# ProProject_485__V11_2025-04-04.net
KiCad netlist of a schematic drawn in EasyEDA Pro
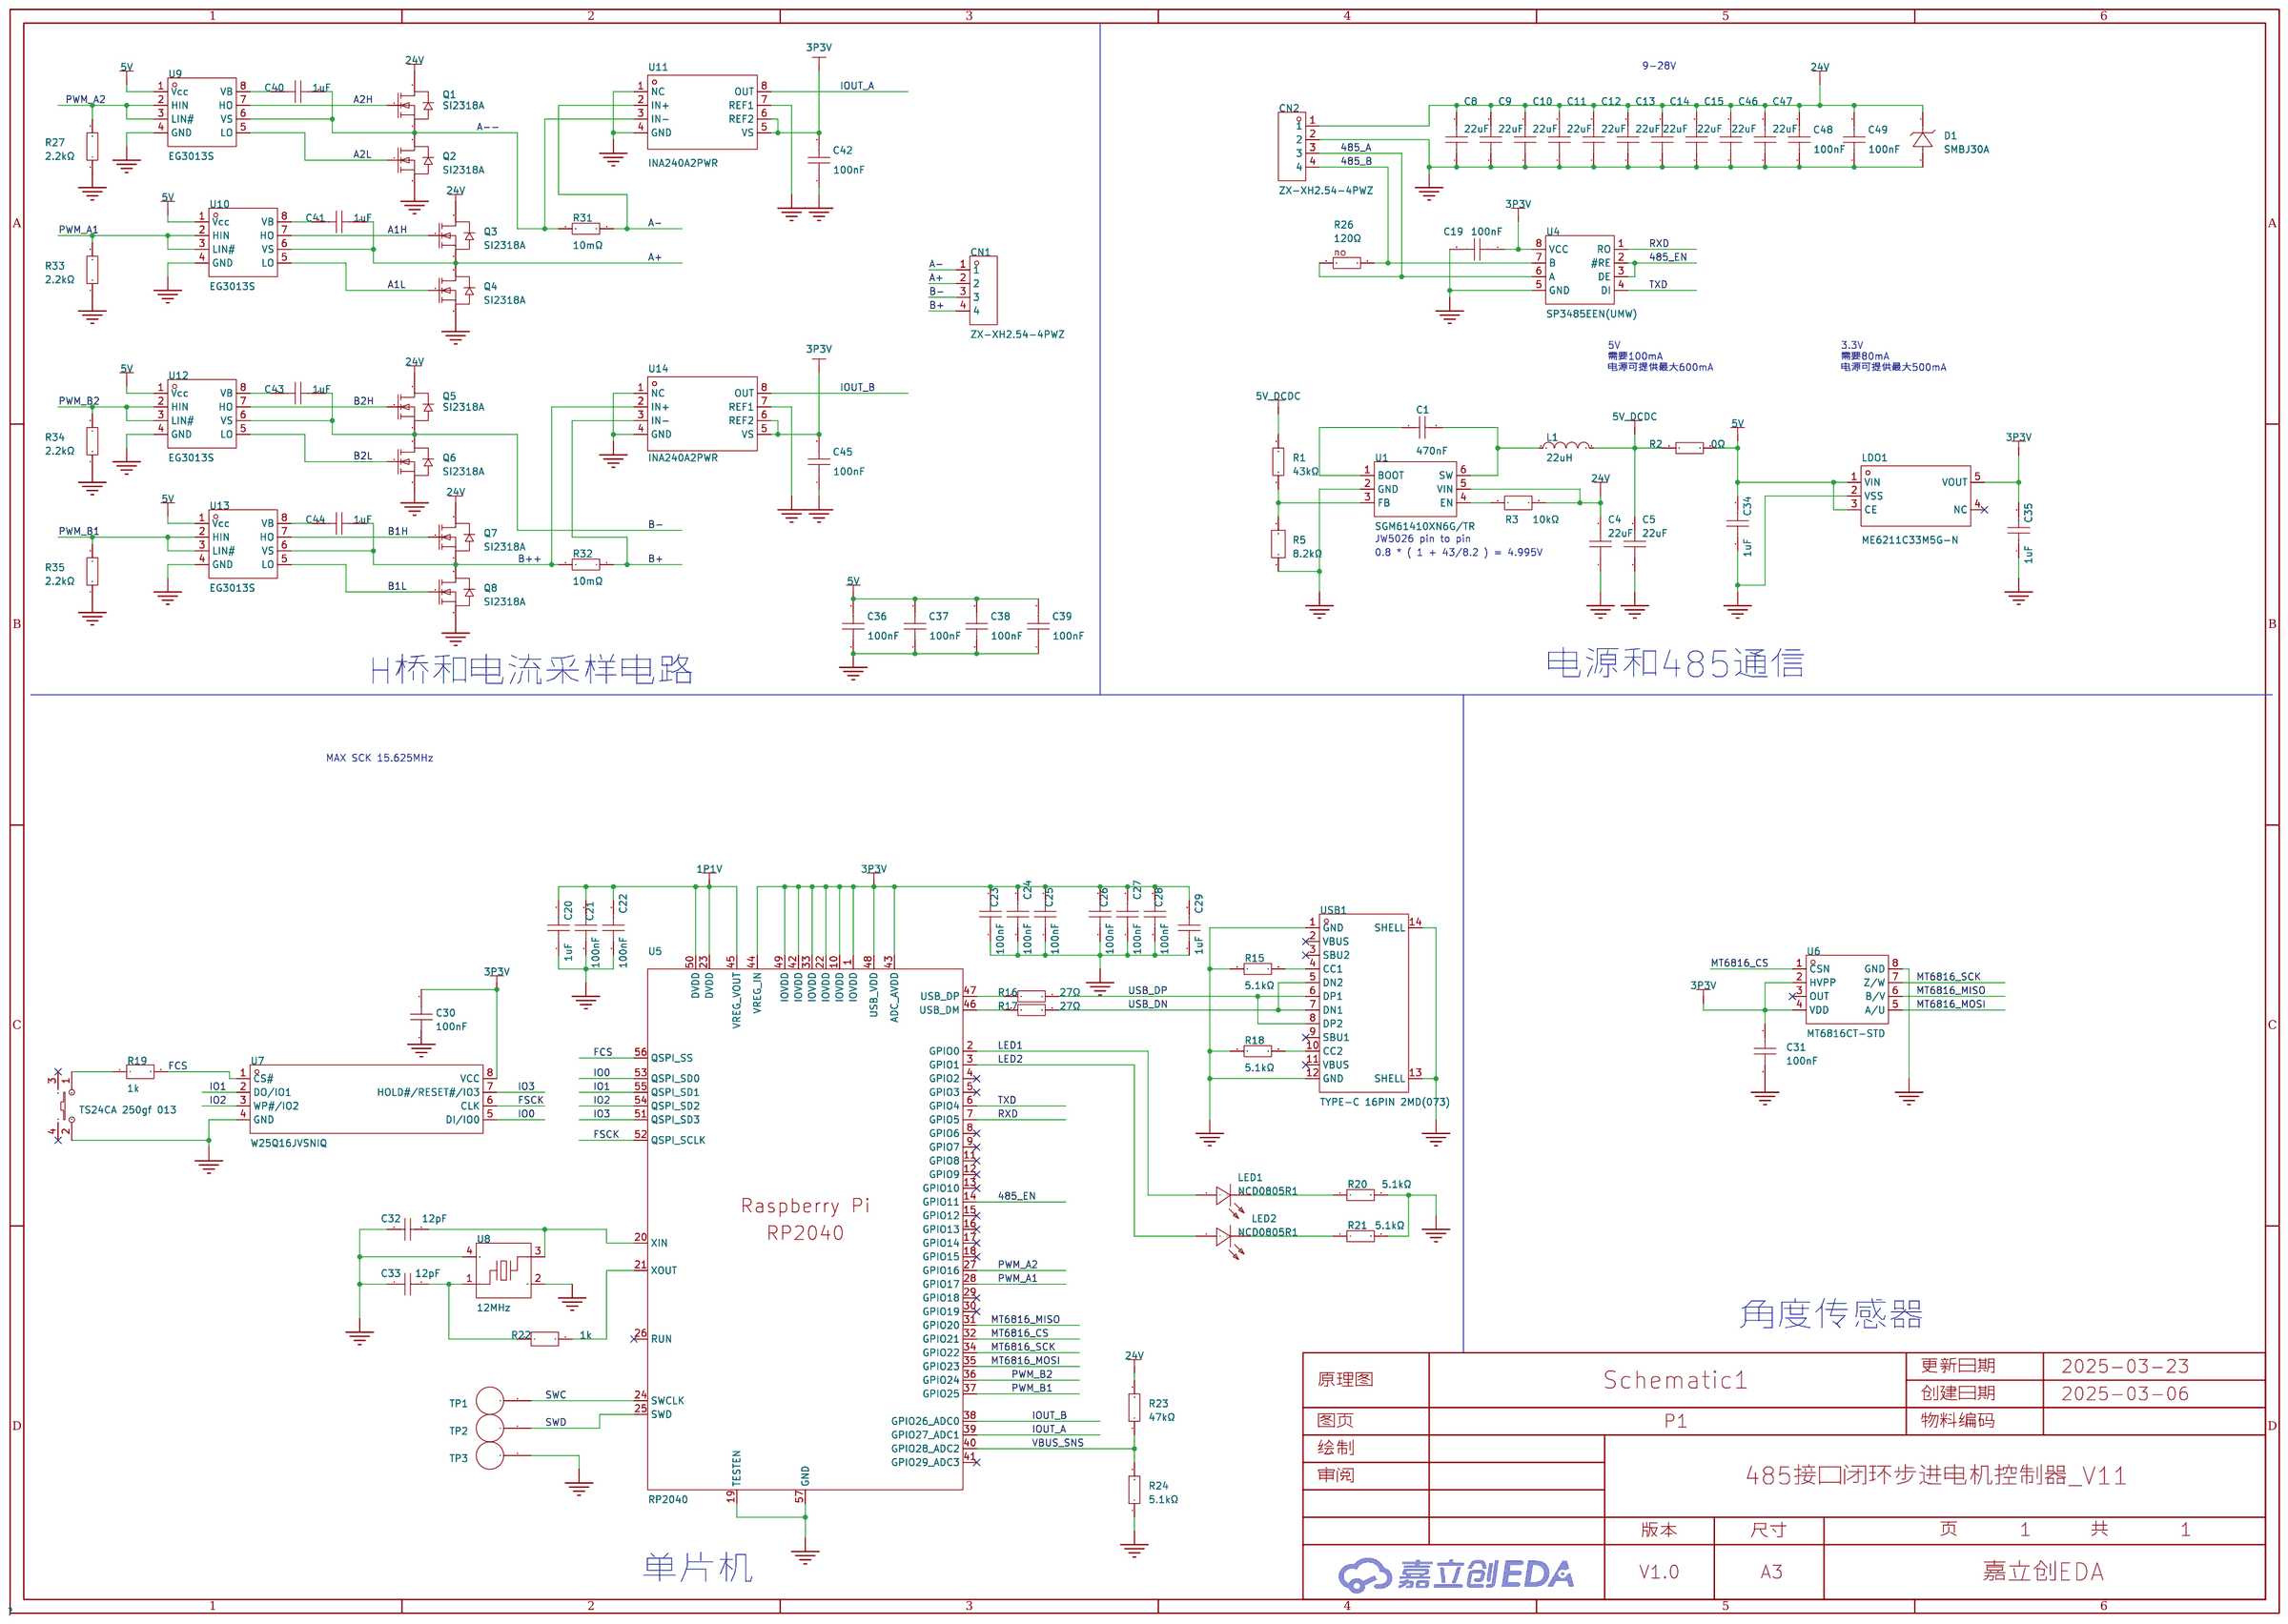
[diagram p0: schematic sheet]

(export (version "E")
  (design (tool "Eeschema 10.0.6"))
  (components
    (comp (ref "C1")
      (value "470nF")
      (footprint "easyedapro:C0603")
      (description "容值:470nF;精度:±10%;额定电压:25V;材质(温度系数):X7R;")
      (fields
        (field (name "Manufacturer Part") "CL10B474KA8NNNC")
        (field (name "Manufacturer") "SAMSUNG(三星)")
      )
      (libsource (lib "easyedapro") (part "CL10B474KA8NNNC"))
    )
    (comp (ref "C4")
      (value "22uF")
      (footprint "easyedapro:C0805")
      (description "容值:22uF;精度:±20%;额定电压:35V;材质(温度系数):X5R;")
      (fields
        (field (name "Manufacturer Part") "CGA0805X5R226M350MT")
        (field (name "Manufacturer") "HRE(芯声)")
      )
      (libsource (lib "easyedapro") (part "CGA0805X5R226M350MT"))
    )
    (comp (ref "C5")
      (value "22uF")
      (footprint "easyedapro:C0805")
      (description "容值:22uF;精度:±20%;额定电压:35V;材质(温度系数):X5R;")
      (fields
        (field (name "Manufacturer Part") "CGA0805X5R226M350MT")
        (field (name "Manufacturer") "HRE(芯声)")
      )
      (libsource (lib "easyedapro") (part "CGA0805X5R226M350MT"))
    )
    (comp (ref "C8")
      (value "22uF")
      (footprint "easyedapro:C0805")
      (description "容值:22uF;精度:±20%;额定电压:35V;材质(温度系数):X5R;")
      (fields
        (field (name "Manufacturer Part") "CGA0805X5R226M350MT")
        (field (name "Manufacturer") "HRE(芯声)")
      )
      (libsource (lib "easyedapro") (part "CGA0805X5R226M350MT"))
    )
    (comp (ref "C9")
      (value "22uF")
      (footprint "easyedapro:C0805")
      (description "容值:22uF;精度:±20%;额定电压:35V;材质(温度系数):X5R;")
      (fields
        (field (name "Manufacturer Part") "CGA0805X5R226M350MT")
        (field (name "Manufacturer") "HRE(芯声)")
      )
      (libsource (lib "easyedapro") (part "CGA0805X5R226M350MT"))
    )
    (comp (ref "C10")
      (value "22uF")
      (footprint "easyedapro:C0805")
      (description "容值:22uF;精度:±20%;额定电压:35V;材质(温度系数):X5R;")
      (fields
        (field (name "Manufacturer Part") "CGA0805X5R226M350MT")
        (field (name "Manufacturer") "HRE(芯声)")
      )
      (libsource (lib "easyedapro") (part "CGA0805X5R226M350MT"))
    )
    (comp (ref "C11")
      (value "22uF")
      (footprint "easyedapro:C0805")
      (description "容值:22uF;精度:±20%;额定电压:35V;材质(温度系数):X5R;")
      (fields
        (field (name "Manufacturer Part") "CGA0805X5R226M350MT")
        (field (name "Manufacturer") "HRE(芯声)")
      )
      (libsource (lib "easyedapro") (part "CGA0805X5R226M350MT"))
    )
    (comp (ref "C12")
      (value "22uF")
      (footprint "easyedapro:C0805")
      (description "容值:22uF;精度:±20%;额定电压:35V;材质(温度系数):X5R;")
      (fields
        (field (name "Manufacturer Part") "CGA0805X5R226M350MT")
        (field (name "Manufacturer") "HRE(芯声)")
      )
      (libsource (lib "easyedapro") (part "CGA0805X5R226M350MT"))
    )
    (comp (ref "C13")
      (value "22uF")
      (footprint "easyedapro:C0805")
      (description "容值:22uF;精度:±20%;额定电压:35V;材质(温度系数):X5R;")
      (fields
        (field (name "Manufacturer Part") "CGA0805X5R226M350MT")
        (field (name "Manufacturer") "HRE(芯声)")
      )
      (libsource (lib "easyedapro") (part "CGA0805X5R226M350MT"))
    )
    (comp (ref "C14")
      (value "22uF")
      (footprint "easyedapro:C0805")
      (description "容值:22uF;精度:±20%;额定电压:35V;材质(温度系数):X5R;")
      (fields
        (field (name "Manufacturer Part") "CGA0805X5R226M350MT")
        (field (name "Manufacturer") "HRE(芯声)")
      )
      (libsource (lib "easyedapro") (part "CGA0805X5R226M350MT"))
    )
    (comp (ref "C15")
      (value "22uF")
      (footprint "easyedapro:C0805")
      (description "容值:22uF;精度:±20%;额定电压:35V;材质(温度系数):X5R;")
      (fields
        (field (name "Manufacturer Part") "CGA0805X5R226M350MT")
        (field (name "Manufacturer") "HRE(芯声)")
      )
      (libsource (lib "easyedapro") (part "CGA0805X5R226M350MT"))
    )
    (comp (ref "C19")
      (value "100nF")
      (footprint "easyedapro:C0603")
      (description "容值:100nF;精度:±10%;额定电压:50V;材质(温度系数):X7R;")
      (fields
        (field (name "Manufacturer Part") "CC0603KRX7R9BB104")
        (field (name "Manufacturer") "YAGEO(国巨)")
      )
      (libsource (lib "easyedapro") (part "CC0603KRX7R9BB104"))
    )
    (comp (ref "C20")
      (value "1uF")
      (footprint "easyedapro:C0603")
      (description "容值:1uF;精度:±10%;额定电压:50V;材质(温度系数):X5R;")
      (fields
        (field (name "Manufacturer Part") "CL10A105KB8NNNC")
        (field (name "Manufacturer") "SAMSUNG(三星)")
      )
      (libsource (lib "easyedapro") (part "CL10A105KB8NNNC"))
    )
    (comp (ref "C21")
      (value "100nF")
      (footprint "easyedapro:C0603")
      (description "容值:100nF;精度:±10%;额定电压:50V;材质(温度系数):X7R;")
      (fields
        (field (name "Manufacturer Part") "CC0603KRX7R9BB104")
        (field (name "Manufacturer") "YAGEO(国巨)")
      )
      (libsource (lib "easyedapro") (part "CC0603KRX7R9BB104"))
    )
    (comp (ref "C22")
      (value "100nF")
      (footprint "easyedapro:C0603")
      (description "容值:100nF;精度:±10%;额定电压:50V;材质(温度系数):X7R;")
      (fields
        (field (name "Manufacturer Part") "CC0603KRX7R9BB104")
        (field (name "Manufacturer") "YAGEO(国巨)")
      )
      (libsource (lib "easyedapro") (part "CC0603KRX7R9BB104"))
    )
    (comp (ref "C23")
      (value "100nF")
      (footprint "easyedapro:C0603")
      (description "容值:100nF;精度:±10%;额定电压:50V;材质(温度系数):X7R;")
      (fields
        (field (name "Manufacturer Part") "CC0603KRX7R9BB104")
        (field (name "Manufacturer") "YAGEO(国巨)")
      )
      (libsource (lib "easyedapro") (part "CC0603KRX7R9BB104"))
    )
    (comp (ref "C24")
      (value "100nF")
      (footprint "easyedapro:C0603")
      (description "容值:100nF;精度:±10%;额定电压:50V;材质(温度系数):X7R;")
      (fields
        (field (name "Manufacturer Part") "CC0603KRX7R9BB104")
        (field (name "Manufacturer") "YAGEO(国巨)")
      )
      (libsource (lib "easyedapro") (part "CC0603KRX7R9BB104"))
    )
    (comp (ref "C25")
      (value "100nF")
      (footprint "easyedapro:C0603")
      (description "容值:100nF;精度:±10%;额定电压:50V;材质(温度系数):X7R;")
      (fields
        (field (name "Manufacturer Part") "CC0603KRX7R9BB104")
        (field (name "Manufacturer") "YAGEO(国巨)")
      )
      (libsource (lib "easyedapro") (part "CC0603KRX7R9BB104"))
    )
    (comp (ref "C26")
      (value "100nF")
      (footprint "easyedapro:C0603")
      (description "容值:100nF;精度:±10%;额定电压:50V;材质(温度系数):X7R;")
      (fields
        (field (name "Manufacturer Part") "CC0603KRX7R9BB104")
        (field (name "Manufacturer") "YAGEO(国巨)")
      )
      (libsource (lib "easyedapro") (part "CC0603KRX7R9BB104"))
    )
    (comp (ref "C27")
      (value "100nF")
      (footprint "easyedapro:C0603")
      (description "容值:100nF;精度:±10%;额定电压:50V;材质(温度系数):X7R;")
      (fields
        (field (name "Manufacturer Part") "CC0603KRX7R9BB104")
        (field (name "Manufacturer") "YAGEO(国巨)")
      )
      (libsource (lib "easyedapro") (part "CC0603KRX7R9BB104"))
    )
    (comp (ref "C28")
      (value "100nF")
      (footprint "easyedapro:C0603")
      (description "容值:100nF;精度:±10%;额定电压:50V;材质(温度系数):X7R;")
      (fields
        (field (name "Manufacturer Part") "CC0603KRX7R9BB104")
        (field (name "Manufacturer") "YAGEO(国巨)")
      )
      (libsource (lib "easyedapro") (part "CC0603KRX7R9BB104"))
    )
    (comp (ref "C29")
      (value "1uF")
      (footprint "easyedapro:C0603")
      (description "容值:1uF;精度:±10%;额定电压:50V;材质(温度系数):X5R;")
      (fields
        (field (name "Manufacturer Part") "CL10A105KB8NNNC")
        (field (name "Manufacturer") "SAMSUNG(三星)")
      )
      (libsource (lib "easyedapro") (part "CL10A105KB8NNNC"))
    )
    (comp (ref "C30")
      (value "100nF")
      (footprint "easyedapro:C0603")
      (description "容值:100nF;精度:±10%;额定电压:50V;材质(温度系数):X7R;")
      (fields
        (field (name "Manufacturer Part") "CC0603KRX7R9BB104")
        (field (name "Manufacturer") "YAGEO(国巨)")
      )
      (libsource (lib "easyedapro") (part "CC0603KRX7R9BB104"))
    )
    (comp (ref "C31")
      (value "100nF")
      (footprint "easyedapro:C0603")
      (description "容值:100nF;精度:±10%;额定电压:50V;材质(温度系数):X7R;")
      (fields
        (field (name "Manufacturer Part") "CC0603KRX7R9BB104")
        (field (name "Manufacturer") "YAGEO(国巨)")
      )
      (libsource (lib "easyedapro") (part "CC0603KRX7R9BB104"))
    )
    (comp (ref "C32")
      (value "12pF")
      (footprint "easyedapro:C0603")
      (description "容值:12pF;精度:±5%;额定电压:50V;材质(温度系数):C0G;")
      (fields
        (field (name "Manufacturer Part") "CL10C120JB8NNNC")
        (field (name "Manufacturer") "SAMSUNG(三星)")
      )
      (libsource (lib "easyedapro") (part "CL10C120JB8NNNC"))
    )
    (comp (ref "C33")
      (value "12pF")
      (footprint "easyedapro:C0603")
      (description "容值:12pF;精度:±5%;额定电压:50V;材质(温度系数):C0G;")
      (fields
        (field (name "Manufacturer Part") "CL10C120JB8NNNC")
        (field (name "Manufacturer") "SAMSUNG(三星)")
      )
      (libsource (lib "easyedapro") (part "CL10C120JB8NNNC"))
    )
    (comp (ref "C34")
      (value "1uF")
      (footprint "easyedapro:C0603")
      (description "容值:1uF;精度:±10%;额定电压:50V;材质(温度系数):X5R;")
      (fields
        (field (name "Manufacturer Part") "CL10A105KB8NNNC")
        (field (name "Manufacturer") "SAMSUNG(三星)")
      )
      (libsource (lib "easyedapro") (part "CL10A105KB8NNNC"))
    )
    (comp (ref "C35")
      (value "1uF")
      (footprint "easyedapro:C0603")
      (description "容值:1uF;精度:±10%;额定电压:50V;材质(温度系数):X5R;")
      (fields
        (field (name "Manufacturer Part") "CL10A105KB8NNNC")
        (field (name "Manufacturer") "SAMSUNG(三星)")
      )
      (libsource (lib "easyedapro") (part "CL10A105KB8NNNC"))
    )
    (comp (ref "C36")
      (value "100nF")
      (footprint "easyedapro:C0603")
      (description "容值:100nF;精度:±10%;额定电压:50V;材质(温度系数):X7R;")
      (fields
        (field (name "Manufacturer Part") "CC0603KRX7R9BB104")
        (field (name "Manufacturer") "YAGEO(国巨)")
      )
      (libsource (lib "easyedapro") (part "CC0603KRX7R9BB104"))
    )
    (comp (ref "C37")
      (value "100nF")
      (footprint "easyedapro:C0603")
      (description "容值:100nF;精度:±10%;额定电压:50V;材质(温度系数):X7R;")
      (fields
        (field (name "Manufacturer Part") "CC0603KRX7R9BB104")
        (field (name "Manufacturer") "YAGEO(国巨)")
      )
      (libsource (lib "easyedapro") (part "CC0603KRX7R9BB104"))
    )
    (comp (ref "C38")
      (value "100nF")
      (footprint "easyedapro:C0603")
      (description "容值:100nF;精度:±10%;额定电压:50V;材质(温度系数):X7R;")
      (fields
        (field (name "Manufacturer Part") "CC0603KRX7R9BB104")
        (field (name "Manufacturer") "YAGEO(国巨)")
      )
      (libsource (lib "easyedapro") (part "CC0603KRX7R9BB104"))
    )
    (comp (ref "C39")
      (value "100nF")
      (footprint "easyedapro:C0603")
      (description "容值:100nF;精度:±10%;额定电压:50V;材质(温度系数):X7R;")
      (fields
        (field (name "Manufacturer Part") "CC0603KRX7R9BB104")
        (field (name "Manufacturer") "YAGEO(国巨)")
      )
      (libsource (lib "easyedapro") (part "CC0603KRX7R9BB104"))
    )
    (comp (ref "C40")
      (value "1uF")
      (footprint "easyedapro:C0603")
      (description "容值:1uF;精度:±10%;额定电压:50V;材质(温度系数):X5R;")
      (fields
        (field (name "Manufacturer Part") "CL10A105KB8NNNC")
        (field (name "Manufacturer") "SAMSUNG(三星)")
      )
      (libsource (lib "easyedapro") (part "CL10A105KB8NNNC"))
    )
    (comp (ref "C41")
      (value "1uF")
      (footprint "easyedapro:C0603")
      (description "容值:1uF;精度:±10%;额定电压:50V;材质(温度系数):X5R;")
      (fields
        (field (name "Manufacturer Part") "CL10A105KB8NNNC")
        (field (name "Manufacturer") "SAMSUNG(三星)")
      )
      (libsource (lib "easyedapro") (part "CL10A105KB8NNNC"))
    )
    (comp (ref "C42")
      (value "100nF")
      (footprint "easyedapro:C0603")
      (description "容值:100nF;精度:±10%;额定电压:50V;材质(温度系数):X7R;")
      (fields
        (field (name "Manufacturer Part") "CC0603KRX7R9BB104")
        (field (name "Manufacturer") "YAGEO(国巨)")
      )
      (libsource (lib "easyedapro") (part "CC0603KRX7R9BB104"))
    )
    (comp (ref "C43")
      (value "1uF")
      (footprint "easyedapro:C0603")
      (description "容值:1uF;精度:±10%;额定电压:50V;材质(温度系数):X5R;")
      (fields
        (field (name "Manufacturer Part") "CL10A105KB8NNNC")
        (field (name "Manufacturer") "SAMSUNG(三星)")
      )
      (libsource (lib "easyedapro") (part "CL10A105KB8NNNC"))
    )
    (comp (ref "C44")
      (value "1uF")
      (footprint "easyedapro:C0603")
      (description "容值:1uF;精度:±10%;额定电压:50V;材质(温度系数):X5R;")
      (fields
        (field (name "Manufacturer Part") "CL10A105KB8NNNC")
        (field (name "Manufacturer") "SAMSUNG(三星)")
      )
      (libsource (lib "easyedapro") (part "CL10A105KB8NNNC"))
    )
    (comp (ref "C45")
      (value "100nF")
      (footprint "easyedapro:C0603")
      (description "容值:100nF;精度:±10%;额定电压:50V;材质(温度系数):X7R;")
      (fields
        (field (name "Manufacturer Part") "CC0603KRX7R9BB104")
        (field (name "Manufacturer") "YAGEO(国巨)")
      )
      (libsource (lib "easyedapro") (part "CC0603KRX7R9BB104"))
    )
    (comp (ref "C46")
      (value "22uF")
      (footprint "easyedapro:C0805")
      (description "容值:22uF;精度:±20%;额定电压:35V;材质(温度系数):X5R;")
      (fields
        (field (name "Manufacturer Part") "CGA0805X5R226M350MT")
        (field (name "Manufacturer") "HRE(芯声)")
      )
      (libsource (lib "easyedapro") (part "CGA0805X5R226M350MT"))
    )
    (comp (ref "C47")
      (value "22uF")
      (footprint "easyedapro:C0805")
      (description "容值:22uF;精度:±20%;额定电压:35V;材质(温度系数):X5R;")
      (fields
        (field (name "Manufacturer Part") "CGA0805X5R226M350MT")
        (field (name "Manufacturer") "HRE(芯声)")
      )
      (libsource (lib "easyedapro") (part "CGA0805X5R226M350MT"))
    )
    (comp (ref "C48")
      (value "100nF")
      (footprint "easyedapro:C0603")
      (description "容值:100nF;精度:±10%;额定电压:50V;材质(温度系数):X7R;")
      (fields
        (field (name "Manufacturer Part") "CC0603KRX7R9BB104")
        (field (name "Manufacturer") "YAGEO(国巨)")
      )
      (libsource (lib "easyedapro") (part "CC0603KRX7R9BB104"))
    )
    (comp (ref "C49")
      (value "100nF")
      (footprint "easyedapro:C0603")
      (description "容值:100nF;精度:±10%;额定电压:50V;材质(温度系数):X7R;")
      (fields
        (field (name "Manufacturer Part") "CC0603KRX7R9BB104")
        (field (name "Manufacturer") "YAGEO(国巨)")
      )
      (libsource (lib "easyedapro") (part "CC0603KRX7R9BB104"))
    )
    (comp (ref "CN1")
      (value "ZX-XH2.54-4PWZ")
      (footprint "easyedapro:CONN-TH_4P-P2.50_ZX-XH2.54-4PWZ")
      (fields (field (name "Manufacturer") "Megastar(兆星)"))
      (libsource (lib "easyedapro") (part "ZX-XH2.54-4PWZ"))
    )
    (comp (ref "CN2")
      (value "ZX-XH2.54-4PWZ")
      (footprint "easyedapro:CONN-TH_4P-P2.50_ZX-XH2.54-4PWZ")
      (fields (field (name "Manufacturer") "Megastar(兆星)"))
      (libsource (lib "easyedapro") (part "ZX-XH2.54-4PWZ"))
    )
    (comp (ref "D1")
      (value "SMBJ30A")
      (footprint "easyedapro:SMB_L4.6-W3.6-LS5.4-RD")
      (description "极性:单向;反向截止电压(Vrwm):30V;钳位电压:48.4V;峰值脉冲电流(Ipp):12.4A;峰值脉冲功率(Ppp):600W;击穿电压:33.3V;")
      (fields (field (name "Manufacturer") "宏嘉诚"))
      (libsource (lib "easyedapro") (part "SMBJ30A_C19077584"))
    )
    (comp (ref "L1")
      (value "22uH")
      (footprint "easyedapro:IND-SMD_L4.0-W4.0")
      (description "电感值:22uH;精度:±20%;额定电流:1.1A;饱和电流(Isat):1.5A;")
      (fields
        (field (name "Manufacturer Part") "FHD4020S-220MT")
        (field (name "Manufacturer") "cjiang(长江微电)")
      )
      (libsource (lib "easyedapro") (part "FHD4020S-220MT"))
    )
    (comp (ref "LDO1")
      (value "ME6211C33M5G-N")
      (footprint "easyedapro:SOT-23-5_L3.0-W1.7-P0.95-LS2.8-BL")
      (description "输出类型:固定;最大输入电压:6V;输出电压:3.3V;最大输出电流:500mA;电源纹波抑制比(PSRR):70dB;输出极性:正极;")
      (fields (field (name "Manufacturer") "MICRONE(南京微盟)"))
      (libsource (lib "easyedapro") (part "ME6211C33M5G-N"))
    )
    (comp (ref "LED1")
      (value "NCD0805R1")
      (footprint "easyedapro:LED0805-R-RD")
      (fields (field (name "Manufacturer") "国星光电"))
      (libsource (lib "easyedapro") (part "FC-2012HRK-620D"))
    )
    (comp (ref "LED2")
      (value "NCD0805R1")
      (footprint "easyedapro:LED0805-R-RD")
      (fields (field (name "Manufacturer") "国星光电"))
      (libsource (lib "easyedapro") (part "FC-2012HRK-620D"))
    )
    (comp (ref "Q1")
      (value "SI2318A")
      (footprint "easyedapro:SOT-23-3_L2.9-W1.3-P1.90-LS2.4-BR")
      (fields (field (name "Manufacturer") "UMW(友台半导体)"))
      (libsource (lib "easyedapro") (part "SI2318A"))
    )
    (comp (ref "Q2")
      (value "SI2318A")
      (footprint "easyedapro:SOT-23-3_L2.9-W1.3-P1.90-LS2.4-BR")
      (fields (field (name "Manufacturer") "UMW(友台半导体)"))
      (libsource (lib "easyedapro") (part "SI2318A"))
    )
    (comp (ref "Q3")
      (value "SI2318A")
      (footprint "easyedapro:SOT-23-3_L2.9-W1.3-P1.90-LS2.4-BR")
      (fields (field (name "Manufacturer") "UMW(友台半导体)"))
      (libsource (lib "easyedapro") (part "SI2318A"))
    )
    (comp (ref "Q4")
      (value "SI2318A")
      (footprint "easyedapro:SOT-23-3_L2.9-W1.3-P1.90-LS2.4-BR")
      (fields (field (name "Manufacturer") "UMW(友台半导体)"))
      (libsource (lib "easyedapro") (part "SI2318A"))
    )
    (comp (ref "Q5")
      (value "SI2318A")
      (footprint "easyedapro:SOT-23-3_L2.9-W1.3-P1.90-LS2.4-BR")
      (fields (field (name "Manufacturer") "UMW(友台半导体)"))
      (libsource (lib "easyedapro") (part "SI2318A"))
    )
    (comp (ref "Q6")
      (value "SI2318A")
      (footprint "easyedapro:SOT-23-3_L2.9-W1.3-P1.90-LS2.4-BR")
      (fields (field (name "Manufacturer") "UMW(友台半导体)"))
      (libsource (lib "easyedapro") (part "SI2318A"))
    )
    (comp (ref "Q7")
      (value "SI2318A")
      (footprint "easyedapro:SOT-23-3_L2.9-W1.3-P1.90-LS2.4-BR")
      (fields (field (name "Manufacturer") "UMW(友台半导体)"))
      (libsource (lib "easyedapro") (part "SI2318A"))
    )
    (comp (ref "Q8")
      (value "SI2318A")
      (footprint "easyedapro:SOT-23-3_L2.9-W1.3-P1.90-LS2.4-BR")
      (fields (field (name "Manufacturer") "UMW(友台半导体)"))
      (libsource (lib "easyedapro") (part "SI2318A"))
    )
    (comp (ref "R1")
      (value "43kΩ")
      (footprint "easyedapro:R0603")
      (description "电阻类型:厚膜电阻;阻值:47kΩ;精度:±1%;功率:100mW;最大工作电压:75V;温度系数:±100ppm/°C;")
      (fields
        (field (name "Manufacturer Part") "0603WAF4302T5E")
        (field (name "Manufacturer") "UNI-ROYAL(厚声)")
      )
      (libsource (lib "easyedapro") (part "0603WAF4702T5E"))
    )
    (comp (ref "R2")
      (value "0Ω")
      (footprint "easyedapro:R0603")
      (description "电阻类型:厚膜电阻;阻值:0Ω;精度:±1%;功率:100mW;最大工作电压:75V;")
      (fields
        (field (name "Manufacturer Part") "0603WAF0000T5E")
        (field (name "Manufacturer") "UNI-ROYAL(厚声)")
      )
      (libsource (lib "easyedapro") (part "0603WAF0000T5E"))
    )
    (comp (ref "R3")
      (value "10kΩ")
      (footprint "easyedapro:R0603")
      (description "电阻类型:薄膜电阻;阻值:10kΩ;精度:±0.1%;功率:100mW;")
      (fields (field (name "Manufacturer Part") "AT0603BRD0710KL") (field (name "Manufacturer") "YAGEO(国巨)"))
      (libsource (lib "easyedapro") (part "AT0603BRD0710KL"))
    )
    (comp (ref "R5")
      (value "8.2kΩ")
      (footprint "easyedapro:R0603")
      (description "电阻类型:厚膜电阻;阻值:15kΩ;精度:±1%;功率:100mW;最大工作电压:75V;温度系数:±100ppm/°C;")
      (fields (field (name "Manufacturer Part") "FRC0603F8201TS") (field (name "Manufacturer") "FOJAN(富捷)"))
      (libsource (lib "easyedapro") (part "FRC0603F1502TS"))
    )
    (comp (ref "R15")
      (value "5.1kΩ")
      (footprint "easyedapro:R0603")
      (description "阻值:5.1kΩ;精度:±1%;功率:100mW;温度系数:±100ppm/°C;电阻类型:厚膜电阻;")
      (fields
        (field (name "Manufacturer Part") "0603WAF5101T5E")
        (field (name "Manufacturer") "UNI-ROYAL(厚声)")
      )
      (libsource (lib "easyedapro") (part "0603WAF5101T5E"))
    )
    (comp (ref "R16")
      (value "27Ω")
      (footprint "easyedapro:R0603")
      (description "精度:±1%;温度系数:±100ppm/°C;阻值:27Ω;功率:100mW;最大工作电压:50V;工作温度范围:-55°C~+155°C;")
      (fields (field (name "Manufacturer Part") "RS-03K27R0FT") (field (name "Manufacturer") "FH(风华)"))
      (libsource (lib "easyedapro") (part "RS-03K27R0FT"))
    )
    (comp (ref "R17")
      (value "27Ω")
      (footprint "easyedapro:R0603")
      (description "精度:±1%;温度系数:±100ppm/°C;阻值:27Ω;功率:100mW;最大工作电压:50V;工作温度范围:-55°C~+155°C;")
      (fields (field (name "Manufacturer Part") "RS-03K27R0FT") (field (name "Manufacturer") "FH(风华)"))
      (libsource (lib "easyedapro") (part "RS-03K27R0FT"))
    )
    (comp (ref "R18")
      (value "5.1kΩ")
      (footprint "easyedapro:R0603")
      (description "阻值:5.1kΩ;精度:±1%;功率:100mW;温度系数:±100ppm/°C;电阻类型:厚膜电阻;")
      (fields
        (field (name "Manufacturer Part") "0603WAF5101T5E")
        (field (name "Manufacturer") "UNI-ROYAL(厚声)")
      )
      (libsource (lib "easyedapro") (part "0603WAF5101T5E"))
    )
    (comp (ref "R19") (value "1k") (footprint "easyedapro:R0603") (libsource (lib "easyedapro") (part "1K")))
    (comp (ref "R20")
      (value "5.1kΩ")
      (footprint "easyedapro:R0603")
      (description "阻值:5.1kΩ;精度:±1%;功率:100mW;温度系数:±100ppm/°C;电阻类型:厚膜电阻;")
      (fields
        (field (name "Manufacturer Part") "0603WAF5101T5E")
        (field (name "Manufacturer") "UNI-ROYAL(厚声)")
      )
      (libsource (lib "easyedapro") (part "0603WAF5101T5E"))
    )
    (comp (ref "R21")
      (value "5.1kΩ")
      (footprint "easyedapro:R0603")
      (description "阻值:5.1kΩ;精度:±1%;功率:100mW;温度系数:±100ppm/°C;电阻类型:厚膜电阻;")
      (fields
        (field (name "Manufacturer Part") "0603WAF5101T5E")
        (field (name "Manufacturer") "UNI-ROYAL(厚声)")
      )
      (libsource (lib "easyedapro") (part "0603WAF5101T5E"))
    )
    (comp (ref "R22") (value "1k") (footprint "easyedapro:R0603") (libsource (lib "easyedapro") (part "1K")))
    (comp (ref "R23")
      (value "47kΩ")
      (footprint "easyedapro:R0603")
      (description "电阻类型:厚膜电阻;阻值:47kΩ;精度:±1%;功率:100mW;最大工作电压:75V;温度系数:±100ppm/°C;")
      (fields
        (field (name "Manufacturer Part") "0603WAF4702T5E")
        (field (name "Manufacturer") "UNI-ROYAL(厚声)")
      )
      (libsource (lib "easyedapro") (part "0603WAF4702T5E"))
    )
    (comp (ref "R24")
      (value "5.1kΩ")
      (footprint "easyedapro:R0603")
      (description "阻值:5.1kΩ;精度:±1%;功率:100mW;温度系数:±100ppm/°C;电阻类型:厚膜电阻;")
      (fields
        (field (name "Manufacturer Part") "0603WAF5101T5E")
        (field (name "Manufacturer") "UNI-ROYAL(厚声)")
      )
      (libsource (lib "easyedapro") (part "0603WAF5101T5E"))
    )
    (comp (ref "R26")
      (value "120Ω")
      (footprint "easyedapro:R0603")
      (description "电阻类型:厚膜电阻;阻值:120Ω;精度:±1%;功率:100mW;最大工作电压:75V;温度系数:±100ppm/°C;")
      (fields
        (field (name "Manufacturer Part") "0603WAF1200T5E")
        (field (name "Manufacturer") "UNI-ROYAL(厚声)")
        (field (name "Add into BOM") "no")
      )
      (libsource (lib "easyedapro") (part "0603WAF1200T5E"))
    )
    (comp (ref "R27")
      (value "2.2kΩ")
      (footprint "easyedapro:R0603")
      (description "阻值:5.1kΩ;精度:±1%;功率:100mW;温度系数:±100ppm/°C;电阻类型:厚膜电阻;")
      (fields
        (field (name "Manufacturer Part") "0603WAF2201T5E")
        (field (name "Manufacturer") "UNI-ROYAL(厚声)")
      )
      (libsource (lib "easyedapro") (part "0603WAF5101T5E"))
    )
    (comp (ref "R31")
      (value "10mΩ")
      (footprint "easyedapro:R0805")
      (description "电阻类型:厚膜电阻;阻值:10mΩ;精度:±1%;功率:250mW;最大工作电压:150V;")
      (fields
        (field (name "Manufacturer Part") "0805W4F100MT5E")
        (field (name "Manufacturer") "UNI-ROYAL(厚声)")
      )
      (libsource (lib "easyedapro") (part "0805W4F100MT5E"))
    )
    (comp (ref "R32")
      (value "10mΩ")
      (footprint "easyedapro:R0805")
      (description "电阻类型:厚膜电阻;阻值:10mΩ;精度:±1%;功率:250mW;最大工作电压:150V;")
      (fields
        (field (name "Manufacturer Part") "0805W4F100MT5E")
        (field (name "Manufacturer") "UNI-ROYAL(厚声)")
      )
      (libsource (lib "easyedapro") (part "0805W4F100MT5E"))
    )
    (comp (ref "R33")
      (value "2.2kΩ")
      (footprint "easyedapro:R0603")
      (description "阻值:5.1kΩ;精度:±1%;功率:100mW;温度系数:±100ppm/°C;电阻类型:厚膜电阻;")
      (fields
        (field (name "Manufacturer Part") "0603WAF2201T5E")
        (field (name "Manufacturer") "UNI-ROYAL(厚声)")
      )
      (libsource (lib "easyedapro") (part "0603WAF5101T5E"))
    )
    (comp (ref "R34")
      (value "2.2kΩ")
      (footprint "easyedapro:R0603")
      (description "阻值:5.1kΩ;精度:±1%;功率:100mW;温度系数:±100ppm/°C;电阻类型:厚膜电阻;")
      (fields
        (field (name "Manufacturer Part") "0603WAF2201T5E")
        (field (name "Manufacturer") "UNI-ROYAL(厚声)")
      )
      (libsource (lib "easyedapro") (part "0603WAF5101T5E"))
    )
    (comp (ref "R35")
      (value "2.2kΩ")
      (footprint "easyedapro:R0603")
      (description "阻值:5.1kΩ;精度:±1%;功率:100mW;温度系数:±100ppm/°C;电阻类型:厚膜电阻;")
      (fields
        (field (name "Manufacturer Part") "0603WAF2201T5E")
        (field (name "Manufacturer") "UNI-ROYAL(厚声)")
      )
      (libsource (lib "easyedapro") (part "0603WAF5101T5E"))
    )
    (comp (ref "SW1")
      (value "TS24CA 250gf 013")
      (footprint "easyedapro:SW-SMD_L4.7-W3.5-P3.35-EH")
      (fields (field (name "Manufacturer") "SHOU HAN(首韩)"))
      (libsource (lib "easyedapro") (part "TS24CA 250GF 013"))
    )
    (comp (ref "TP1") (value "~") (footprint "easyedapro:TP") (libsource (lib "easyedapro") (part "TP")))
    (comp (ref "TP2") (value "~") (footprint "easyedapro:TP") (libsource (lib "easyedapro") (part "TP")))
    (comp (ref "TP3") (value "~") (footprint "easyedapro:TP") (libsource (lib "easyedapro") (part "TP")))
    (comp (ref "U1")
      (value "SGM61410XN6G/TR")
      (footprint "easyedapro:TSOT-23-6_L2.9-W1.6-P0.95-LS2.8-BL")
      (fields (field (name "Manufacturer") "SGMICRO(圣邦微)"))
      (libsource (lib "easyedapro") (part "SGM61410XN6G/TR"))
    )
    (comp (ref "U4")
      (value "SP3485EEN(UMW)")
      (footprint "easyedapro:SOP-8_L5.0-W4.0-P1.27-LS6.0-BL")
      (description "类型:收发器;数据速率:12Mbps;")
      (fields (field (name "Manufacturer") "UMW(友台半导体)"))
      (libsource (lib "easyedapro") (part "SP3485EEN"))
    )
    (comp (ref "U5")
      (value "RP2040")
      (footprint "easyedapro:LQFN-56_L7.0-W7.0-P0.4-EP")
      (description "CPU内核:ARM-M系列;CPU最大主频:133MHz;程序存储容量:-;程序存储器类型:-;GPIO端口数量:30;工作电压范围:-;RAM总容量:264KB;应用领域:-;")
      (fields (field (name "Manufacturer") "Raspberry Pi(树莓派)"))
      (libsource (lib "easyedapro") (part "RP2040"))
    )
    (comp (ref "U6")
      (value "MT6816CT-STD")
      (footprint "easyedapro:SOP-8_L4.9-W3.9-P1.27-LS6.0-BL")
      (description "零延迟磁角位置传感器IC")
      (fields (field (name "Manufacturer") "MagnTek(麦歌恩)"))
      (libsource (lib "easyedapro") (part "MT6816CT-STD"))
    )
    (comp (ref "U7")
      (value "W25Q16JVSNIQ")
      (footprint "easyedapro:SOP-8_L4.9-W3.9-P1.27-LS6.0-BL")
      (fields (field (name "Manufacturer") "WINBOND(华邦)"))
      (libsource (lib "easyedapro") (part "W25Q16JVSNIQ TR"))
    )
    (comp (ref "U8")
      (value "12MHz")
      (footprint "easyedapro:CRYSTAL-SMD_4P-L3.2-W2.5-BL_SIT8008BI")
      (description "晶振类型:贴片晶振;频率:12MHz;常温频差:±10ppm;外接负载电容:12pF;频率稳定度(全温):±30ppm;")
      (fields (field (name "Manufacturer Part") "CF4012M00012001") (field (name "Manufacturer") "HUAXIN(华昕)"))
      (libsource (lib "easyedapro") (part "CF4012M00012001"))
    )
    (comp (ref "U9")
      (value "EG3013S")
      (footprint "easyedapro:SOP-8_L4.9-W3.9-P1.27-LS6.0-BL-1")
      (fields (field (name "Manufacturer") "EG(屹晶微)"))
      (libsource (lib "easyedapro") (part "EG3013S"))
    )
    (comp (ref "U10")
      (value "EG3013S")
      (footprint "easyedapro:SOP-8_L4.9-W3.9-P1.27-LS6.0-BL-1")
      (fields (field (name "Manufacturer") "EG(屹晶微)"))
      (libsource (lib "easyedapro") (part "EG3013S"))
    )
    (comp (ref "U11")
      (value "INA240A2PWR")
      (footprint "easyedapro:TSSOP-8_L4.4-W3.0-P0.65-LS6.4-BL")
      (description "放大器数:单路;")
      (fields (field (name "Manufacturer") "TI(德州仪器)"))
      (libsource (lib "easyedapro") (part "INA240A2PWR"))
    )
    (comp (ref "U12")
      (value "EG3013S")
      (footprint "easyedapro:SOP-8_L4.9-W3.9-P1.27-LS6.0-BL-1")
      (fields (field (name "Manufacturer") "EG(屹晶微)"))
      (libsource (lib "easyedapro") (part "EG3013S"))
    )
    (comp (ref "U13")
      (value "EG3013S")
      (footprint "easyedapro:SOP-8_L4.9-W3.9-P1.27-LS6.0-BL-1")
      (fields (field (name "Manufacturer") "EG(屹晶微)"))
      (libsource (lib "easyedapro") (part "EG3013S"))
    )
    (comp (ref "U14")
      (value "INA240A2PWR")
      (footprint "easyedapro:TSSOP-8_L4.4-W3.0-P0.65-LS6.4-BL")
      (description "放大器数:单路;")
      (fields (field (name "Manufacturer") "TI(德州仪器)"))
      (libsource (lib "easyedapro") (part "INA240A2PWR"))
    )
    (comp (ref "USB1")
      (value "TYPE-C 16PIN 2MD(073)")
      (footprint "easyedapro:USB-C-SMD_TYPE-C-6PIN-2MD-073")
      (description "连接器类型:Type-C;标准:-;公母:母;触点数量:16P;端口数量:1;安装方式:卧贴;额定电流 - 电源:5A;工作温度范围:-25°C~+85°C;")
      (fields (field (name "Manufacturer") "SHOU HAN(首韩)"))
      (libsource (lib "easyedapro") (part "TYPE-C 16PIN 2MD(073)"))
    )
  )
  (nets
    (net (code "1") (name "/485_A") (class "Default")
      (node (ref "CN2") (pin "3") (pinfunction "3_3") (pintype "unspecified"))
      (node (ref "R26") (pin "1") (pinfunction "1_1") (pintype "input"))
      (node (ref "U4") (pin "6") (pinfunction "A_6") (pintype "unspecified"))
    )
    (net (code "2") (name "/485_B") (class "Default")
      (node (ref "CN2") (pin "4") (pinfunction "4_4") (pintype "unspecified"))
      (node (ref "R26") (pin "2") (pinfunction "2_2") (pintype "input"))
      (node (ref "U4") (pin "7") (pinfunction "B_7") (pintype "unspecified"))
    )
    (net (code "3") (name "/485_EN") (class "Default")
      (node (ref "U4") (pin "2") (pinfunction "#RE_2") (pintype "unspecified"))
      (node (ref "U4") (pin "3") (pinfunction "DE_3") (pintype "unspecified"))
      (node (ref "U5") (pin "14") (pinfunction "GPIO11_14") (pintype "bidirectional"))
    )
    (net (code "4") (name "/A+") (class "Default")
      (node (ref "C41") (pin "1") (pinfunction "1_1") (pintype "unspecified"))
      (node (ref "CN1") (pin "2") (pinfunction "2_2") (pintype "unspecified"))
      (node (ref "Q3") (pin "2") (pinfunction "S_2") (pintype "unspecified"))
      (node (ref "Q4") (pin "3") (pinfunction "D_3") (pintype "unspecified"))
      (node (ref "U10") (pin "6") (pinfunction "VS_6") (pintype "unspecified"))
    )
    (net (code "5") (name "/A-") (class "Default")
      (node (ref "CN1") (pin "1") (pinfunction "1_1") (pintype "unspecified"))
      (node (ref "R31") (pin "2") (pinfunction "2_2") (pintype "unspecified"))
      (node (ref "U11") (pin "2") (pinfunction "IN+_2") (pintype "unspecified"))
    )
    (net (code "6") (name "/A--") (class "Default")
      (node (ref "C40") (pin "1") (pinfunction "1_1") (pintype "unspecified"))
      (node (ref "Q1") (pin "2") (pinfunction "S_2") (pintype "unspecified"))
      (node (ref "Q2") (pin "3") (pinfunction "D_3") (pintype "unspecified"))
      (node (ref "R31") (pin "1") (pinfunction "1_1") (pintype "unspecified"))
      (node (ref "U11") (pin "3") (pinfunction "IN-_3") (pintype "unspecified"))
      (node (ref "U9") (pin "6") (pinfunction "VS_6") (pintype "unspecified"))
    )
    (net (code "7") (name "/A1H") (class "Default")
      (node (ref "Q3") (pin "1") (pinfunction "G_1") (pintype "unspecified"))
      (node (ref "U10") (pin "7") (pinfunction "HO_7") (pintype "unspecified"))
    )
    (net (code "8") (name "/A1L") (class "Default")
      (node (ref "Q4") (pin "1") (pinfunction "G_1") (pintype "unspecified"))
      (node (ref "U10") (pin "5") (pinfunction "LO_5") (pintype "unspecified"))
    )
    (net (code "9") (name "/A2H") (class "Default")
      (node (ref "Q1") (pin "1") (pinfunction "G_1") (pintype "unspecified"))
      (node (ref "U9") (pin "7") (pinfunction "HO_7") (pintype "unspecified"))
    )
    (net (code "10") (name "/A2L") (class "Default")
      (node (ref "Q2") (pin "1") (pinfunction "G_1") (pintype "unspecified"))
      (node (ref "U9") (pin "5") (pinfunction "LO_5") (pintype "unspecified"))
    )
    (net (code "11") (name "/B+") (class "Default")
      (node (ref "CN1") (pin "4") (pinfunction "4_4") (pintype "unspecified"))
      (node (ref "R32") (pin "2") (pinfunction "2_2") (pintype "unspecified"))
      (node (ref "U14") (pin "3") (pinfunction "IN-_3") (pintype "unspecified"))
    )
    (net (code "12") (name "/B++") (class "Default")
      (node (ref "C44") (pin "1") (pinfunction "1_1") (pintype "unspecified"))
      (node (ref "Q7") (pin "2") (pinfunction "S_2") (pintype "unspecified"))
      (node (ref "Q8") (pin "3") (pinfunction "D_3") (pintype "unspecified"))
      (node (ref "R32") (pin "1") (pinfunction "1_1") (pintype "unspecified"))
      (node (ref "U13") (pin "6") (pinfunction "VS_6") (pintype "unspecified"))
      (node (ref "U14") (pin "2") (pinfunction "IN+_2") (pintype "unspecified"))
    )
    (net (code "13") (name "/B-") (class "Default")
      (node (ref "C43") (pin "1") (pinfunction "1_1") (pintype "unspecified"))
      (node (ref "CN1") (pin "3") (pinfunction "3_3") (pintype "unspecified"))
      (node (ref "Q5") (pin "2") (pinfunction "S_2") (pintype "unspecified"))
      (node (ref "Q6") (pin "3") (pinfunction "D_3") (pintype "unspecified"))
      (node (ref "U12") (pin "6") (pinfunction "VS_6") (pintype "unspecified"))
    )
    (net (code "14") (name "/B1H") (class "Default")
      (node (ref "Q7") (pin "1") (pinfunction "G_1") (pintype "unspecified"))
      (node (ref "U13") (pin "7") (pinfunction "HO_7") (pintype "unspecified"))
    )
    (net (code "15") (name "/B1L") (class "Default")
      (node (ref "Q8") (pin "1") (pinfunction "G_1") (pintype "unspecified"))
      (node (ref "U13") (pin "5") (pinfunction "LO_5") (pintype "unspecified"))
    )
    (net (code "16") (name "/B2H") (class "Default")
      (node (ref "Q5") (pin "1") (pinfunction "G_1") (pintype "unspecified"))
      (node (ref "U12") (pin "7") (pinfunction "HO_7") (pintype "unspecified"))
    )
    (net (code "17") (name "/B2L") (class "Default")
      (node (ref "Q6") (pin "1") (pinfunction "G_1") (pintype "unspecified"))
      (node (ref "U12") (pin "5") (pinfunction "LO_5") (pintype "unspecified"))
    )
    (net (code "18") (name "/FCS") (class "Default")
      (node (ref "R19") (pin "2") (pinfunction "2_2") (pintype "unspecified"))
      (node (ref "U5") (pin "56") (pinfunction "QSPI_SS_56") (pintype "bidirectional"))
      (node (ref "U7") (pin "1") (pinfunction "CS#_1") (pintype "unspecified"))
    )
    (net (code "19") (name "/FSCK") (class "Default")
      (node (ref "U5") (pin "52") (pinfunction "QSPI_SCLK_52") (pintype "output"))
      (node (ref "U7") (pin "6") (pinfunction "CLK_6") (pintype "unspecified"))
    )
    (net (code "20") (name "/IO0") (class "Default")
      (node (ref "U5") (pin "53") (pinfunction "QSPI_SD0_53") (pintype "bidirectional"))
      (node (ref "U7") (pin "5") (pinfunction "DI/IO0_5") (pintype "unspecified"))
    )
    (net (code "21") (name "/IO1") (class "Default")
      (node (ref "U5") (pin "55") (pinfunction "QSPI_SD1_55") (pintype "bidirectional"))
      (node (ref "U7") (pin "2") (pinfunction "DO/IO1_2") (pintype "unspecified"))
    )
    (net (code "22") (name "/IO2") (class "Default")
      (node (ref "U5") (pin "54") (pinfunction "QSPI_SD2_54") (pintype "bidirectional"))
      (node (ref "U7") (pin "3") (pinfunction "WP#/IO2_3") (pintype "unspecified"))
    )
    (net (code "23") (name "/IO3") (class "Default")
      (node (ref "U5") (pin "51") (pinfunction "QSPI_SD3_51") (pintype "bidirectional"))
      (node (ref "U7") (pin "7") (pinfunction "HOLD#/RESET#/IO3_7") (pintype "unspecified"))
    )
    (net (code "24") (name "/IOUT_A") (class "Default")
      (node (ref "U11") (pin "8") (pinfunction "OUT_8") (pintype "unspecified"))
      (node (ref "U5") (pin "39") (pinfunction "GPIO27_ADC1_39") (pintype "bidirectional"))
    )
    (net (code "25") (name "/IOUT_B") (class "Default")
      (node (ref "U14") (pin "8") (pinfunction "OUT_8") (pintype "unspecified"))
      (node (ref "U5") (pin "38") (pinfunction "GPIO26_ADC0_38") (pintype "bidirectional"))
    )
    (net (code "26") (name "/LED1") (class "Default")
      (node (ref "LED1") (pin "1") (pinfunction "+_1") (pintype "unspecified"))
      (node (ref "U5") (pin "2") (pinfunction "GPIO0_2") (pintype "bidirectional"))
    )
    (net (code "27") (name "/LED2") (class "Default")
      (node (ref "LED2") (pin "1") (pinfunction "+_1") (pintype "unspecified"))
      (node (ref "U5") (pin "3") (pinfunction "GPIO1_3") (pintype "bidirectional"))
    )
    (net (code "28") (name "/MT6816_CS") (class "Default")
      (node (ref "U5") (pin "32") (pinfunction "GPIO21_32") (pintype "bidirectional"))
      (node (ref "U6") (pin "1") (pinfunction "CSN_1") (pintype "unspecified"))
    )
    (net (code "29") (name "/MT6816_MISO") (class "Default")
      (node (ref "U5") (pin "31") (pinfunction "GPIO20_31") (pintype "bidirectional"))
      (node (ref "U6") (pin "6") (pinfunction "B/V_6") (pintype "unspecified"))
    )
    (net (code "30") (name "/MT6816_MOSI") (class "Default")
      (node (ref "U5") (pin "35") (pinfunction "GPIO23_35") (pintype "bidirectional"))
      (node (ref "U6") (pin "5") (pinfunction "A/U_5") (pintype "unspecified"))
    )
    (net (code "31") (name "/MT6816_SCK") (class "Default")
      (node (ref "U5") (pin "34") (pinfunction "GPIO22_34") (pintype "bidirectional"))
      (node (ref "U6") (pin "7") (pinfunction "Z/W_7") (pintype "unspecified"))
    )
    (net (code "32") (name "/PWM_A1") (class "Default")
      (node (ref "R33") (pin "2") (pinfunction "2_2") (pintype "input"))
      (node (ref "U10") (pin "2") (pinfunction "HIN_2") (pintype "unspecified"))
      (node (ref "U10") (pin "3") (pinfunction "LIN#_3") (pintype "unspecified"))
      (node (ref "U5") (pin "28") (pinfunction "GPIO17_28") (pintype "bidirectional"))
    )
    (net (code "33") (name "/PWM_A2") (class "Default")
      (node (ref "R27") (pin "2") (pinfunction "2_2") (pintype "input"))
      (node (ref "U5") (pin "27") (pinfunction "GPIO16_27") (pintype "bidirectional"))
      (node (ref "U9") (pin "2") (pinfunction "HIN_2") (pintype "unspecified"))
      (node (ref "U9") (pin "3") (pinfunction "LIN#_3") (pintype "unspecified"))
    )
    (net (code "34") (name "/PWM_B1") (class "Default")
      (node (ref "R35") (pin "2") (pinfunction "2_2") (pintype "input"))
      (node (ref "U13") (pin "2") (pinfunction "HIN_2") (pintype "unspecified"))
      (node (ref "U13") (pin "3") (pinfunction "LIN#_3") (pintype "unspecified"))
      (node (ref "U5") (pin "37") (pinfunction "GPIO25_37") (pintype "bidirectional"))
    )
    (net (code "35") (name "/PWM_B2") (class "Default")
      (node (ref "R34") (pin "2") (pinfunction "2_2") (pintype "input"))
      (node (ref "U12") (pin "2") (pinfunction "HIN_2") (pintype "unspecified"))
      (node (ref "U12") (pin "3") (pinfunction "LIN#_3") (pintype "unspecified"))
      (node (ref "U5") (pin "36") (pinfunction "GPIO24_36") (pintype "bidirectional"))
    )
    (net (code "36") (name "/RXD") (class "Default")
      (node (ref "U4") (pin "1") (pinfunction "RO_1") (pintype "unspecified"))
      (node (ref "U5") (pin "7") (pinfunction "GPIO5_7") (pintype "bidirectional"))
    )
    (net (code "37") (name "/SWC") (class "Default")
      (node (ref "TP1") (pin "1") (pinfunction "1_1") (pintype "input"))
      (node (ref "U5") (pin "24") (pinfunction "SWCLK_24") (pintype "output"))
    )
    (net (code "38") (name "/SWD") (class "Default")
      (node (ref "TP2") (pin "1") (pinfunction "1_1") (pintype "input"))
      (node (ref "U5") (pin "25") (pinfunction "SWD_25") (pintype "bidirectional"))
    )
    (net (code "39") (name "/TXD") (class "Default")
      (node (ref "U4") (pin "4") (pinfunction "DI_4") (pintype "unspecified"))
      (node (ref "U5") (pin "6") (pinfunction "GPIO4_6") (pintype "bidirectional"))
    )
    (net (code "40") (name "/USB_DN") (class "Default")
      (node (ref "R17") (pin "2") (pinfunction "2_2") (pintype "unspecified"))
      (node (ref "USB1") (pin "5") (pinfunction "DN2_5") (pintype "unspecified"))
      (node (ref "USB1") (pin "7") (pinfunction "DN1_7") (pintype "unspecified"))
    )
    (net (code "41") (name "/USB_DP") (class "Default")
      (node (ref "R16") (pin "2") (pinfunction "2_2") (pintype "unspecified"))
      (node (ref "USB1") (pin "6") (pinfunction "DP1_6") (pintype "unspecified"))
      (node (ref "USB1") (pin "8") (pinfunction "DP2_8") (pintype "unspecified"))
    )
    (net (code "42") (name "/VBUS_SNS") (class "Default")
      (node (ref "R23") (pin "1") (pinfunction "1_1") (pintype "input"))
      (node (ref "R24") (pin "2") (pinfunction "2_2") (pintype "input"))
      (node (ref "U5") (pin "40") (pinfunction "GPIO28_ADC2_40") (pintype "bidirectional"))
    )
    (net (code "43") (name "1P1V") (class "Default")
      (node (ref "C20") (pin "2") (pinfunction "2_2") (pintype "unspecified"))
      (node (ref "C21") (pin "2") (pinfunction "2_2") (pintype "unspecified"))
      (node (ref "C22") (pin "2") (pinfunction "2_2") (pintype "unspecified"))
      (node (ref "U5") (pin "23") (pinfunction "DVDD_23") (pintype "bidirectional"))
      (node (ref "U5") (pin "45") (pinfunction "VREG_VOUT_45") (pintype "bidirectional"))
      (node (ref "U5") (pin "50") (pinfunction "DVDD_50") (pintype "bidirectional"))
    )
    (net (code "44") (name "3P3V") (class "Default")
      (node (ref "C19") (pin "1") (pinfunction "1_1") (pintype "unspecified"))
      (node (ref "C23") (pin "2") (pinfunction "2_2") (pintype "unspecified"))
      (node (ref "C24") (pin "2") (pinfunction "2_2") (pintype "unspecified"))
      (node (ref "C25") (pin "2") (pinfunction "2_2") (pintype "unspecified"))
      (node (ref "C26") (pin "2") (pinfunction "2_2") (pintype "unspecified"))
      (node (ref "C27") (pin "2") (pinfunction "2_2") (pintype "unspecified"))
      (node (ref "C28") (pin "2") (pinfunction "2_2") (pintype "unspecified"))
      (node (ref "C29") (pin "2") (pinfunction "2_2") (pintype "unspecified"))
      (node (ref "C30") (pin "2") (pinfunction "2_2") (pintype "unspecified"))
      (node (ref "C31") (pin "1") (pinfunction "1_1") (pintype "unspecified"))
      (node (ref "C35") (pin "2") (pinfunction "2_2") (pintype "unspecified"))
      (node (ref "C42") (pin "2") (pinfunction "2_2") (pintype "unspecified"))
      (node (ref "C45") (pin "2") (pinfunction "2_2") (pintype "unspecified"))
      (node (ref "LDO1") (pin "5") (pinfunction "VOUT_5") (pintype "input"))
      (node (ref "U11") (pin "5") (pinfunction "VS_5") (pintype "unspecified"))
      (node (ref "U11") (pin "6") (pinfunction "REF2_6") (pintype "unspecified"))
      (node (ref "U14") (pin "5") (pinfunction "VS_5") (pintype "unspecified"))
      (node (ref "U14") (pin "6") (pinfunction "REF2_6") (pintype "unspecified"))
      (node (ref "U4") (pin "8") (pinfunction "VCC_8") (pintype "unspecified"))
      (node (ref "U5") (pin "1") (pinfunction "IOVDD_1") (pintype "bidirectional"))
      (node (ref "U5") (pin "10") (pinfunction "IOVDD_10") (pintype "bidirectional"))
      (node (ref "U5") (pin "22") (pinfunction "IOVDD_22") (pintype "bidirectional"))
      (node (ref "U5") (pin "33") (pinfunction "IOVDD_33") (pintype "bidirectional"))
      (node (ref "U5") (pin "42") (pinfunction "IOVDD_42") (pintype "bidirectional"))
      (node (ref "U5") (pin "43") (pinfunction "ADC_AVDD_43") (pintype "bidirectional"))
      (node (ref "U5") (pin "44") (pinfunction "VREG_IN_44") (pintype "bidirectional"))
      (node (ref "U5") (pin "48") (pinfunction "USB_VDD_48") (pintype "bidirectional"))
      (node (ref "U5") (pin "49") (pinfunction "IOVDD_49") (pintype "bidirectional"))
      (node (ref "U6") (pin "2") (pinfunction "HVPP_2") (pintype "unspecified"))
      (node (ref "U6") (pin "4") (pinfunction "VDD_4") (pintype "unspecified"))
      (node (ref "U7") (pin "8") (pinfunction "VCC_8") (pintype "unspecified"))
    )
    (net (code "45") (name "5V") (class "Default")
      (node (ref "C34") (pin "2") (pinfunction "2_2") (pintype "unspecified"))
      (node (ref "C36") (pin "2") (pinfunction "2_2") (pintype "unspecified"))
      (node (ref "C37") (pin "2") (pinfunction "2_2") (pintype "unspecified"))
      (node (ref "C38") (pin "2") (pinfunction "2_2") (pintype "unspecified"))
      (node (ref "C39") (pin "2") (pinfunction "2_2") (pintype "unspecified"))
      (node (ref "LDO1") (pin "1") (pinfunction "VIN_1") (pintype "input"))
      (node (ref "LDO1") (pin "3") (pinfunction "CE_3") (pintype "input"))
      (node (ref "R2") (pin "2") (pinfunction "2_2") (pintype "input"))
      (node (ref "U10") (pin "1") (pinfunction "Vcc_1") (pintype "unspecified"))
      (node (ref "U12") (pin "1") (pinfunction "Vcc_1") (pintype "unspecified"))
      (node (ref "U13") (pin "1") (pinfunction "Vcc_1") (pintype "unspecified"))
      (node (ref "U9") (pin "1") (pinfunction "Vcc_1") (pintype "unspecified"))
    )
    (net (code "46") (name "5V_DCDC") (class "Default")
      (node (ref "C5") (pin "2") (pinfunction "2_2") (pintype "unspecified"))
      (node (ref "L1") (pin "2") (pinfunction "2_2") (pintype "unspecified"))
      (node (ref "R1") (pin "2") (pinfunction "2_2") (pintype "input"))
      (node (ref "R2") (pin "1") (pinfunction "1_1") (pintype "input"))
    )
    (net (code "47") (name "24V") (class "Default")
      (node (ref "C10") (pin "2") (pinfunction "2_2") (pintype "unspecified"))
      (node (ref "C11") (pin "2") (pinfunction "2_2") (pintype "unspecified"))
      (node (ref "C12") (pin "2") (pinfunction "2_2") (pintype "unspecified"))
      (node (ref "C13") (pin "2") (pinfunction "2_2") (pintype "unspecified"))
      (node (ref "C14") (pin "2") (pinfunction "2_2") (pintype "unspecified"))
      (node (ref "C15") (pin "2") (pinfunction "2_2") (pintype "unspecified"))
      (node (ref "C4") (pin "2") (pinfunction "2_2") (pintype "unspecified"))
      (node (ref "C46") (pin "2") (pinfunction "2_2") (pintype "unspecified"))
      (node (ref "C47") (pin "2") (pinfunction "2_2") (pintype "unspecified"))
      (node (ref "C48") (pin "2") (pinfunction "2_2") (pintype "unspecified"))
      (node (ref "C49") (pin "2") (pinfunction "2_2") (pintype "unspecified"))
      (node (ref "C8") (pin "2") (pinfunction "2_2") (pintype "unspecified"))
      (node (ref "C9") (pin "2") (pinfunction "2_2") (pintype "unspecified"))
      (node (ref "CN2") (pin "1") (pinfunction "1_1") (pintype "unspecified"))
      (node (ref "D1") (pin "1") (pinfunction "K_1") (pintype "unspecified"))
      (node (ref "Q1") (pin "3") (pinfunction "D_3") (pintype "unspecified"))
      (node (ref "Q3") (pin "3") (pinfunction "D_3") (pintype "unspecified"))
      (node (ref "Q5") (pin "3") (pinfunction "D_3") (pintype "unspecified"))
      (node (ref "Q7") (pin "3") (pinfunction "D_3") (pintype "unspecified"))
      (node (ref "R23") (pin "2") (pinfunction "2_2") (pintype "input"))
      (node (ref "R3") (pin "2") (pinfunction "2_2") (pintype "unspecified"))
      (node (ref "U1") (pin "5") (pinfunction "VIN_5") (pintype "unspecified"))
    )
    (net (code "48") (name "GND") (class "Default")
      (node (ref "C10") (pin "1") (pinfunction "1_1") (pintype "unspecified"))
      (node (ref "C11") (pin "1") (pinfunction "1_1") (pintype "unspecified"))
      (node (ref "C12") (pin "1") (pinfunction "1_1") (pintype "unspecified"))
      (node (ref "C13") (pin "1") (pinfunction "1_1") (pintype "unspecified"))
      (node (ref "C14") (pin "1") (pinfunction "1_1") (pintype "unspecified"))
      (node (ref "C15") (pin "1") (pinfunction "1_1") (pintype "unspecified"))
      (node (ref "C19") (pin "2") (pinfunction "2_2") (pintype "unspecified"))
      (node (ref "C20") (pin "1") (pinfunction "1_1") (pintype "unspecified"))
      (node (ref "C21") (pin "1") (pinfunction "1_1") (pintype "unspecified"))
      (node (ref "C22") (pin "1") (pinfunction "1_1") (pintype "unspecified"))
      (node (ref "C23") (pin "1") (pinfunction "1_1") (pintype "unspecified"))
      (node (ref "C24") (pin "1") (pinfunction "1_1") (pintype "unspecified"))
      (node (ref "C25") (pin "1") (pinfunction "1_1") (pintype "unspecified"))
      (node (ref "C26") (pin "1") (pinfunction "1_1") (pintype "unspecified"))
      (node (ref "C27") (pin "1") (pinfunction "1_1") (pintype "unspecified"))
      (node (ref "C28") (pin "1") (pinfunction "1_1") (pintype "unspecified"))
      (node (ref "C29") (pin "1") (pinfunction "1_1") (pintype "unspecified"))
      (node (ref "C30") (pin "1") (pinfunction "1_1") (pintype "unspecified"))
      (node (ref "C31") (pin "2") (pinfunction "2_2") (pintype "unspecified"))
      (node (ref "C32") (pin "1") (pinfunction "1_1") (pintype "input"))
      (node (ref "C33") (pin "1") (pinfunction "1_1") (pintype "input"))
      (node (ref "C34") (pin "1") (pinfunction "1_1") (pintype "unspecified"))
      (node (ref "C35") (pin "1") (pinfunction "1_1") (pintype "unspecified"))
      (node (ref "C36") (pin "1") (pinfunction "1_1") (pintype "unspecified"))
      (node (ref "C37") (pin "1") (pinfunction "1_1") (pintype "unspecified"))
      (node (ref "C38") (pin "1") (pinfunction "1_1") (pintype "unspecified"))
      (node (ref "C39") (pin "1") (pinfunction "1_1") (pintype "unspecified"))
      (node (ref "C4") (pin "1") (pinfunction "1_1") (pintype "unspecified"))
      (node (ref "C42") (pin "1") (pinfunction "1_1") (pintype "unspecified"))
      (node (ref "C45") (pin "1") (pinfunction "1_1") (pintype "unspecified"))
      (node (ref "C46") (pin "1") (pinfunction "1_1") (pintype "unspecified"))
      (node (ref "C47") (pin "1") (pinfunction "1_1") (pintype "unspecified"))
      (node (ref "C48") (pin "1") (pinfunction "1_1") (pintype "unspecified"))
      (node (ref "C49") (pin "1") (pinfunction "1_1") (pintype "unspecified"))
      (node (ref "C5") (pin "1") (pinfunction "1_1") (pintype "unspecified"))
      (node (ref "C8") (pin "1") (pinfunction "1_1") (pintype "unspecified"))
      (node (ref "C9") (pin "1") (pinfunction "1_1") (pintype "unspecified"))
      (node (ref "CN2") (pin "2") (pinfunction "2_2") (pintype "unspecified"))
      (node (ref "D1") (pin "2") (pinfunction "A_2") (pintype "unspecified"))
      (node (ref "LDO1") (pin "2") (pinfunction "VSS_2") (pintype "input"))
      (node (ref "Q2") (pin "2") (pinfunction "S_2") (pintype "unspecified"))
      (node (ref "Q4") (pin "2") (pinfunction "S_2") (pintype "unspecified"))
      (node (ref "Q6") (pin "2") (pinfunction "S_2") (pintype "unspecified"))
      (node (ref "Q8") (pin "2") (pinfunction "S_2") (pintype "unspecified"))
      (node (ref "R15") (pin "1") (pinfunction "1_1") (pintype "input"))
      (node (ref "R18") (pin "1") (pinfunction "1_1") (pintype "input"))
      (node (ref "R20") (pin "2") (pinfunction "2_2") (pintype "input"))
      (node (ref "R21") (pin "2") (pinfunction "2_2") (pintype "input"))
      (node (ref "R24") (pin "1") (pinfunction "1_1") (pintype "input"))
      (node (ref "R27") (pin "1") (pinfunction "1_1") (pintype "input"))
      (node (ref "R33") (pin "1") (pinfunction "1_1") (pintype "input"))
      (node (ref "R34") (pin "1") (pinfunction "1_1") (pintype "input"))
      (node (ref "R35") (pin "1") (pinfunction "1_1") (pintype "input"))
      (node (ref "R5") (pin "1") (pinfunction "1_1") (pintype "unspecified"))
      (node (ref "SW1") (pin "2") (pinfunction "2_2") (pintype "unspecified"))
      (node (ref "TP3") (pin "1") (pinfunction "1_1") (pintype "input"))
      (node (ref "U1") (pin "2") (pinfunction "GND_2") (pintype "unspecified"))
      (node (ref "U10") (pin "4") (pinfunction "GND_4") (pintype "unspecified"))
      (node (ref "U11") (pin "1") (pinfunction "NC_1") (pintype "unspecified"))
      (node (ref "U11") (pin "4") (pinfunction "GND_4") (pintype "unspecified"))
      (node (ref "U11") (pin "7") (pinfunction "REF1_7") (pintype "unspecified"))
      (node (ref "U12") (pin "4") (pinfunction "GND_4") (pintype "unspecified"))
      (node (ref "U13") (pin "4") (pinfunction "GND_4") (pintype "unspecified"))
      (node (ref "U14") (pin "1") (pinfunction "NC_1") (pintype "unspecified"))
      (node (ref "U14") (pin "4") (pinfunction "GND_4") (pintype "unspecified"))
      (node (ref "U14") (pin "7") (pinfunction "REF1_7") (pintype "unspecified"))
      (node (ref "U4") (pin "5") (pinfunction "GND_5") (pintype "unspecified"))
      (node (ref "U5") (pin "19") (pinfunction "TESTEN_19") (pintype "unspecified"))
      (node (ref "U5") (pin "57") (pinfunction "GND_57") (pintype "bidirectional"))
      (node (ref "U6") (pin "8") (pinfunction "GND_8") (pintype "unspecified"))
      (node (ref "U7") (pin "4") (pinfunction "GND_4") (pintype "unspecified"))
      (node (ref "U8") (pin "2") (pinfunction "GND_2") (pintype "input"))
      (node (ref "U8") (pin "4") (pinfunction "GND_4") (pintype "input"))
      (node (ref "U9") (pin "4") (pinfunction "GND_4") (pintype "unspecified"))
      (node (ref "USB1") (pin "1") (pinfunction "GND_1") (pintype "unspecified"))
      (node (ref "USB1") (pin "12") (pinfunction "GND_12") (pintype "unspecified"))
      (node (ref "USB1") (pin "13") (pinfunction "SHELL_13") (pintype "unspecified"))
      (node (ref "USB1") (pin "14") (pinfunction "SHELL_14") (pintype "unspecified"))
    )
    (net (code "49") (name "Net-(C33-Pad2)") (class "Default")
      (node (ref "C33") (pin "2") (pinfunction "2_2") (pintype "input"))
      (node (ref "R22") (pin "1") (pinfunction "1_1") (pintype "unspecified"))
      (node (ref "U8") (pin "1") (pinfunction "1_1") (pintype "input"))
    )
    (net (code "50") (name "Net-(LED1--)") (class "Default")
      (node (ref "LED1") (pin "2") (pinfunction "-_2") (pintype "unspecified"))
      (node (ref "R20") (pin "1") (pinfunction "1_1") (pintype "input"))
    )
    (net (code "51") (name "Net-(LED2--)") (class "Default")
      (node (ref "LED2") (pin "2") (pinfunction "-_2") (pintype "unspecified"))
      (node (ref "R21") (pin "1") (pinfunction "1_1") (pintype "input"))
    )
    (net (code "52") (name "Net-(R19-Pad1)") (class "Default")
      (node (ref "R19") (pin "1") (pinfunction "1_1") (pintype "unspecified"))
      (node (ref "SW1") (pin "1") (pinfunction "1_1") (pintype "unspecified"))
    )
    (net (code "53") (name "Net-(U1-BOOT)") (class "Default")
      (node (ref "C1") (pin "1") (pinfunction "1_1") (pintype "input"))
      (node (ref "U1") (pin "1") (pinfunction "BOOT_1") (pintype "unspecified"))
    )
    (net (code "54") (name "Net-(U1-EN)") (class "Default")
      (node (ref "R3") (pin "1") (pinfunction "1_1") (pintype "unspecified"))
      (node (ref "U1") (pin "4") (pinfunction "EN_4") (pintype "unspecified"))
    )
    (net (code "55") (name "Net-(U1-FB)") (class "Default")
      (node (ref "R1") (pin "1") (pinfunction "1_1") (pintype "input"))
      (node (ref "R5") (pin "2") (pinfunction "2_2") (pintype "unspecified"))
      (node (ref "U1") (pin "3") (pinfunction "FB_3") (pintype "unspecified"))
    )
    (net (code "56") (name "Net-(U1-SW)") (class "Default")
      (node (ref "C1") (pin "2") (pinfunction "2_2") (pintype "input"))
      (node (ref "L1") (pin "1") (pinfunction "1_1") (pintype "unspecified"))
      (node (ref "U1") (pin "6") (pinfunction "SW_6") (pintype "unspecified"))
    )
    (net (code "57") (name "Net-(U5-USB_DM)") (class "Default")
      (node (ref "R17") (pin "1") (pinfunction "1_1") (pintype "unspecified"))
      (node (ref "U5") (pin "46") (pinfunction "USB_DM_46") (pintype "bidirectional"))
    )
    (net (code "58") (name "Net-(U5-USB_DP)") (class "Default")
      (node (ref "R16") (pin "1") (pinfunction "1_1") (pintype "unspecified"))
      (node (ref "U5") (pin "47") (pinfunction "USB_DP_47") (pintype "bidirectional"))
    )
    (net (code "59") (name "Net-(U5-XIN)") (class "Default")
      (node (ref "C32") (pin "2") (pinfunction "2_2") (pintype "input"))
      (node (ref "U5") (pin "20") (pinfunction "XIN_20") (pintype "input"))
      (node (ref "U8") (pin "3") (pinfunction "3_3") (pintype "input"))
    )
    (net (code "60") (name "Net-(U5-XOUT)") (class "Default")
      (node (ref "R22") (pin "2") (pinfunction "2_2") (pintype "unspecified"))
      (node (ref "U5") (pin "21") (pinfunction "XOUT_21") (pintype "unspecified"))
    )
    (net (code "61") (name "Net-(U9-VB)") (class "Default")
      (node (ref "C40") (pin "2") (pinfunction "2_2") (pintype "unspecified"))
      (node (ref "U9") (pin "8") (pinfunction "VB_8") (pintype "unspecified"))
    )
    (net (code "62") (name "Net-(U10-VB)") (class "Default")
      (node (ref "C41") (pin "2") (pinfunction "2_2") (pintype "unspecified"))
      (node (ref "U10") (pin "8") (pinfunction "VB_8") (pintype "unspecified"))
    )
    (net (code "63") (name "Net-(U12-VB)") (class "Default")
      (node (ref "C43") (pin "2") (pinfunction "2_2") (pintype "unspecified"))
      (node (ref "U12") (pin "8") (pinfunction "VB_8") (pintype "unspecified"))
    )
    (net (code "64") (name "Net-(U13-VB)") (class "Default")
      (node (ref "C44") (pin "2") (pinfunction "2_2") (pintype "unspecified"))
      (node (ref "U13") (pin "8") (pinfunction "VB_8") (pintype "unspecified"))
    )
    (net (code "65") (name "Net-(USB1-CC1)") (class "Default")
      (node (ref "R15") (pin "2") (pinfunction "2_2") (pintype "input"))
      (node (ref "USB1") (pin "4") (pinfunction "CC1_4") (pintype "unspecified"))
    )
    (net (code "66") (name "Net-(USB1-CC2)") (class "Default")
      (node (ref "R18") (pin "2") (pinfunction "2_2") (pintype "input"))
      (node (ref "USB1") (pin "10") (pinfunction "CC2_10") (pintype "unspecified"))
    )
    (net (code "67") (name "unconnected-(LDO1-NC-Pad4)") (class "Default")
      (node (ref "LDO1") (pin "4") (pinfunction "NC_4") (pintype "input+no_connect"))
    )
    (net (code "68") (name "unconnected-(SW1-Pad3)") (class "Default")
      (node (ref "SW1") (pin "3") (pinfunction "3_3") (pintype "unspecified+no_connect"))
    )
    (net (code "69") (name "unconnected-(SW1-Pad4)") (class "Default")
      (node (ref "SW1") (pin "4") (pinfunction "4_4") (pintype "unspecified+no_connect"))
    )
    (net (code "70") (name "unconnected-(U5-GPIO2-Pad4)") (class "Default")
      (node (ref "U5") (pin "4") (pinfunction "GPIO2_4") (pintype "bidirectional+no_connect"))
    )
    (net (code "71") (name "unconnected-(U5-GPIO3-Pad5)") (class "Default")
      (node (ref "U5") (pin "5") (pinfunction "GPIO3_5") (pintype "bidirectional+no_connect"))
    )
    (net (code "72") (name "unconnected-(U5-GPIO6-Pad8)") (class "Default")
      (node (ref "U5") (pin "8") (pinfunction "GPIO6_8") (pintype "bidirectional+no_connect"))
    )
    (net (code "73") (name "unconnected-(U5-GPIO7-Pad9)") (class "Default")
      (node (ref "U5") (pin "9") (pinfunction "GPIO7_9") (pintype "bidirectional+no_connect"))
    )
    (net (code "74") (name "unconnected-(U5-GPIO8-Pad11)") (class "Default")
      (node (ref "U5") (pin "11") (pinfunction "GPIO8_11") (pintype "bidirectional+no_connect"))
    )
    (net (code "75") (name "unconnected-(U5-GPIO9-Pad12)") (class "Default")
      (node (ref "U5") (pin "12") (pinfunction "GPIO9_12") (pintype "bidirectional+no_connect"))
    )
    (net (code "76") (name "unconnected-(U5-GPIO10-Pad13)") (class "Default")
      (node (ref "U5") (pin "13") (pinfunction "GPIO10_13") (pintype "bidirectional+no_connect"))
    )
    (net (code "77") (name "unconnected-(U5-GPIO12-Pad15)") (class "Default")
      (node (ref "U5") (pin "15") (pinfunction "GPIO12_15") (pintype "bidirectional+no_connect"))
    )
    (net (code "78") (name "unconnected-(U5-GPIO13-Pad16)") (class "Default")
      (node (ref "U5") (pin "16") (pinfunction "GPIO13_16") (pintype "bidirectional+no_connect"))
    )
    (net (code "79") (name "unconnected-(U5-GPIO14-Pad17)") (class "Default")
      (node (ref "U5") (pin "17") (pinfunction "GPIO14_17") (pintype "bidirectional+no_connect"))
    )
    (net (code "80") (name "unconnected-(U5-GPIO15-Pad18)") (class "Default")
      (node (ref "U5") (pin "18") (pinfunction "GPIO15_18") (pintype "bidirectional+no_connect"))
    )
    (net (code "81") (name "unconnected-(U5-GPIO18-Pad29)") (class "Default")
      (node (ref "U5") (pin "29") (pinfunction "GPIO18_29") (pintype "bidirectional+no_connect"))
    )
    (net (code "82") (name "unconnected-(U5-GPIO19-Pad30)") (class "Default")
      (node (ref "U5") (pin "30") (pinfunction "GPIO19_30") (pintype "bidirectional+no_connect"))
    )
    (net (code "83") (name "unconnected-(U5-GPIO29_ADC3-Pad41)") (class "Default")
      (node (ref "U5") (pin "41") (pinfunction "GPIO29_ADC3_41") (pintype "bidirectional+no_connect"))
    )
    (net (code "84") (name "unconnected-(U5-RUN-Pad26)") (class "Default")
      (node (ref "U5") (pin "26") (pinfunction "RUN_26") (pintype "input+no_connect"))
    )
    (net (code "85") (name "unconnected-(U6-OUT-Pad3)") (class "Default")
      (node (ref "U6") (pin "3") (pinfunction "OUT_3") (pintype "unspecified+no_connect"))
    )
    (net (code "86") (name "unconnected-(USB1-SBU1-Pad9)") (class "Default")
      (node (ref "USB1") (pin "9") (pinfunction "SBU1_9") (pintype "unspecified+no_connect"))
    )
    (net (code "87") (name "unconnected-(USB1-SBU2-Pad3)") (class "Default")
      (node (ref "USB1") (pin "3") (pinfunction "SBU2_3") (pintype "unspecified+no_connect"))
    )
    (net (code "88") (name "unconnected-(USB1-VBUS-Pad2)") (class "Default")
      (node (ref "USB1") (pin "2") (pinfunction "VBUS_2") (pintype "unspecified+no_connect"))
    )
    (net (code "89") (name "unconnected-(USB1-VBUS-Pad11)") (class "Default")
      (node (ref "USB1") (pin "11") (pinfunction "VBUS_11") (pintype "unspecified+no_connect"))
    )
  )
)
